# 05_-_CPU_-_PCIE.net
KiCad netlist of a schematic drawn in Altium Designer
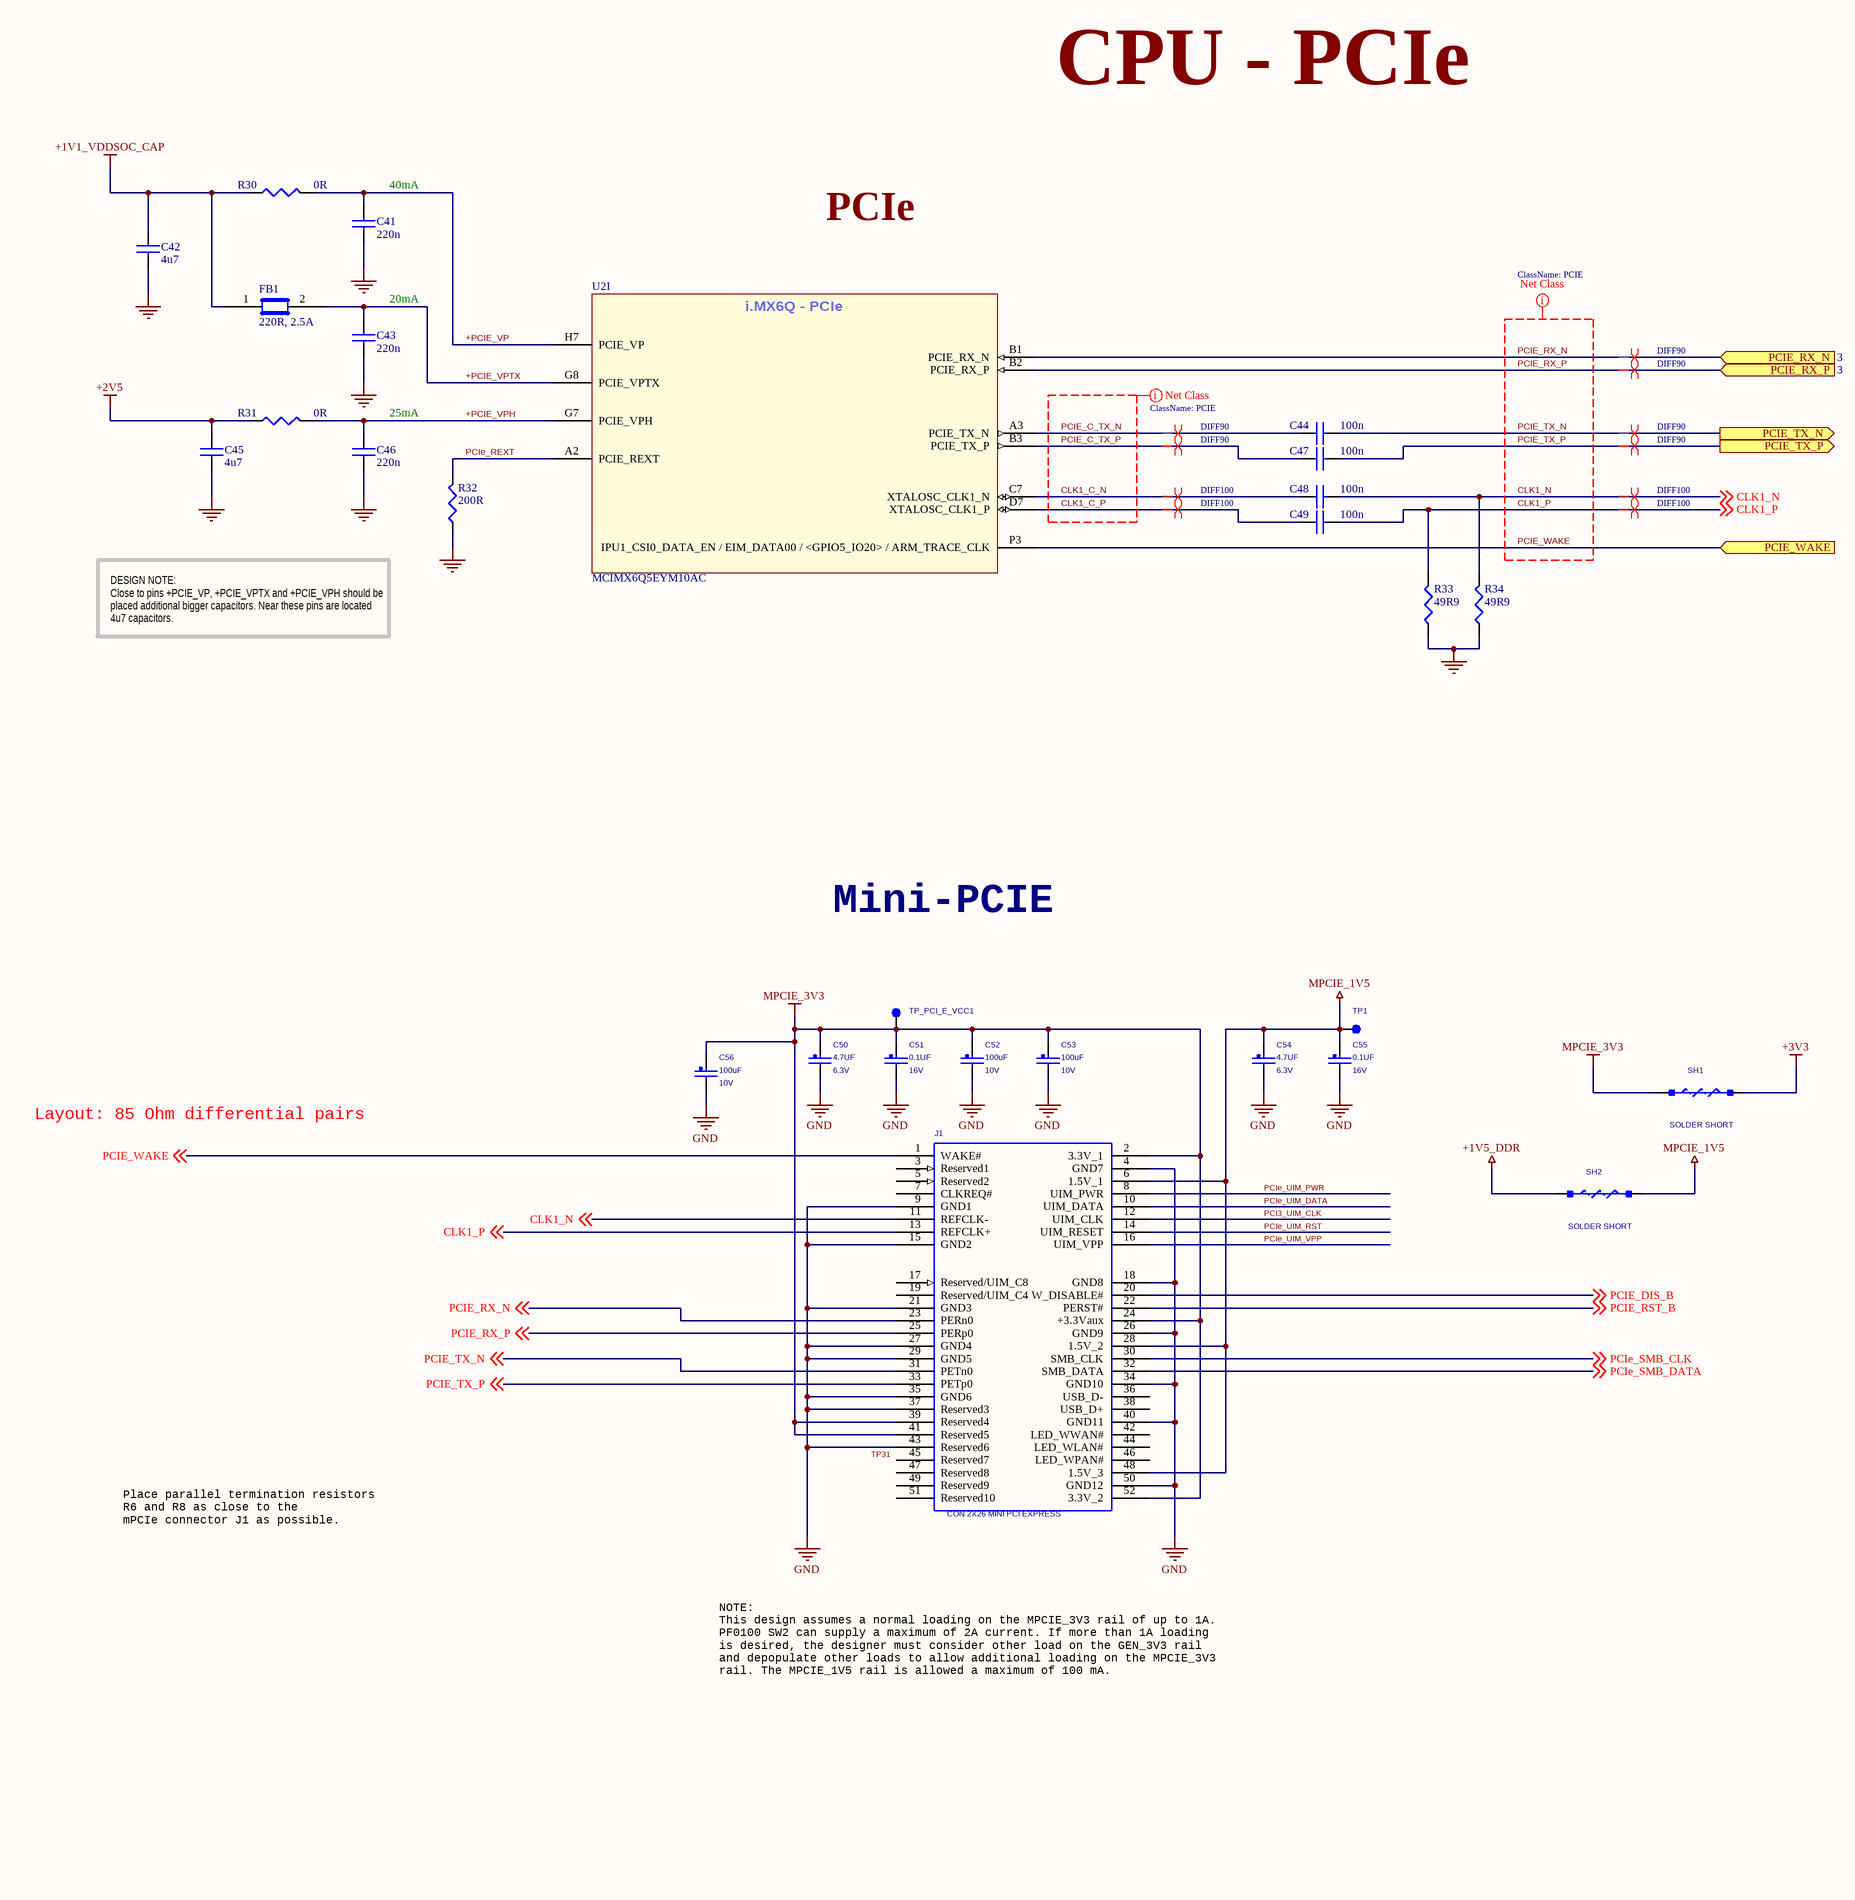
[diagram p0: [05] - CPU - PCIE.SchDoc, left]
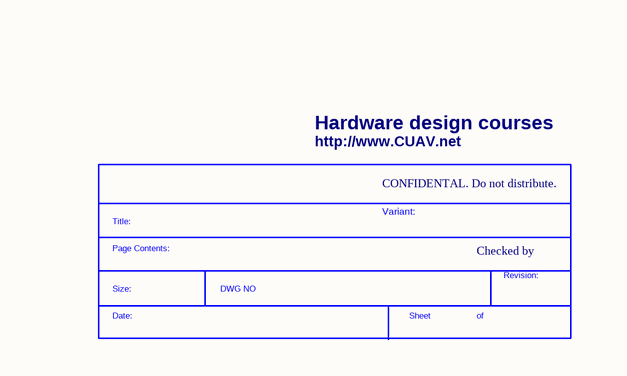
[diagram p1: [05] - CPU - PCIE.SchDoc, right]

(export (version "E")
  (design (tool "Eeschema 10.0.6"))
  (components
    (comp (ref "*") (value "SDTitleBlock") (libsource (lib "*") (part "SDTitleBlock")))
    (comp (ref "C41")
      (value "220n")
      (footprint "C0402")
      (description "CAP CER .22UF 25V X5R 20% 0402")
      (fields
        (field (name "MANUFACTURER") "TDK Corporation")
        (field (name "MANUFACTURER PART NUMBER") "C1005X5R1E224M")
      )
      (libsource (lib "Integrated_Library_RF_FEB_2012") (part "C1005X5R1E224M"))
    )
    (comp (ref "C42")
      (value "4u7")
      (footprint "0603c")
      (description "CAP CER 4.7UF 10V 20% X5R 0402")
      (fields
        (field (name "MANUFACTURER") "TDK Corporation")
        (field (name "MANUFACTURER PART NUMBER") "C1005X5R1A475M")
        (field (name ".CHECKED PCB") "RF")
        (field (name ".CHECKED SCH") "RF")
      )
      (libsource (lib "Integrated_Library_RF_FEB_2012") (part "C1005X5R1A475M"))
    )
    (comp (ref "C43")
      (value "220n")
      (footprint "C0402")
      (description "CAP CER .22UF 25V X5R 20% 0402")
      (fields
        (field (name "MANUFACTURER") "TDK Corporation")
        (field (name "MANUFACTURER PART NUMBER") "C1005X5R1E224M")
      )
      (libsource (lib "Integrated_Library_RF_FEB_2012") (part "C1005X5R1E224M"))
    )
    (comp (ref "C44")
      (value "100n")
      (footprint "C0402")
      (description "CAP CER .10UF 50V X5R 10% 0402")
      (fields
        (field (name "MANUFACTURER") "TDK Corporation")
        (field (name "MANUFACTURER PART NUMBER") "C1005X5R1H104K")
      )
      (libsource (lib "Integrated_Library_RF_FEB_2012") (part "C1005X5R1H104K"))
    )
    (comp (ref "C45")
      (value "4u7")
      (footprint "C0402")
      (description "CAP CER 4.7UF 10V 20% X5R 0402")
      (fields
        (field (name "MANUFACTURER") "TDK Corporation")
        (field (name "MANUFACTURER PART NUMBER") "C1005X5R1A475M")
        (field (name ".CHECKED PCB") "RF")
        (field (name ".CHECKED SCH") "RF")
      )
      (libsource (lib "Integrated_Library_RF_FEB_2012") (part "C1005X5R1A475M"))
    )
    (comp (ref "C46")
      (value "220n")
      (footprint "C0402")
      (description "CAP CER .22UF 25V X5R 20% 0402")
      (fields
        (field (name "MANUFACTURER") "TDK Corporation")
        (field (name "MANUFACTURER PART NUMBER") "C1005X5R1E224M")
      )
      (libsource (lib "Integrated_Library_RF_FEB_2012") (part "C1005X5R1E224M"))
    )
    (comp (ref "C47")
      (value "100n")
      (footprint "C0402")
      (description "CAP CER .10UF 50V X5R 10% 0402")
      (fields
        (field (name "MANUFACTURER") "TDK Corporation")
        (field (name "MANUFACTURER PART NUMBER") "C1005X5R1H104K")
      )
      (libsource (lib "Integrated_Library_RF_FEB_2012") (part "C1005X5R1H104K"))
    )
    (comp (ref "C48")
      (value "100n")
      (footprint "0402cap")
      (description "CAP CER .10UF 50V X5R 10% 0402")
      (fields
        (field (name "MANUFACTURER") "TDK Corporation")
        (field (name "MANUFACTURER PART NUMBER") "C1005X5R1H104K")
      )
      (libsource (lib "Integrated_Library_RF_FEB_2012") (part "C1005X5R1H104K"))
    )
    (comp (ref "C49")
      (value "100n")
      (footprint "0402cap")
      (description "CAP CER .10UF 50V X5R 10% 0402")
      (fields
        (field (name "MANUFACTURER") "TDK Corporation")
        (field (name "MANUFACTURER PART NUMBER") "C1005X5R1H104K")
      )
      (libsource (lib "Integrated_Library_RF_FEB_2012") (part "C1005X5R1H104K"))
    )
    (comp (ref "C50")
      (value "4.7UF")
      (description "CAP CER 4.7UF 6.3V 10% X5R 0603")
      (fields (field (name "TOLERANCE") "10%") (field (name "WVDC") "6.3V") (field (name "VOLTAGE") "6.3V"))
      (libsource (lib "*") (part "CAP_NP"))
    )
    (comp (ref "C51")
      (value "0.1UF")
      (description "CAP CER 0.1UF 16V 10% X7R 0402")
      (fields (field (name "TOLERANCE") "10%") (field (name "WVDC") "16V") (field (name "VOLTAGE") "16V"))
      (libsource (lib "*") (part "CAP_NP"))
    )
    (comp (ref "C52")
      (value "100uF")
      (description "CAP CER 100uF 10V 20% X5R 1206")
      (fields (field (name "TOLERANCE") "20%") (field (name "WVDC") "10V") (field (name "VOLTAGE") "10V"))
      (libsource (lib "*") (part "CAP_NP"))
    )
    (comp (ref "C53")
      (value "100uF")
      (description "CAP CER 100uF 10V 20% X5R 1206")
      (fields (field (name "TOLERANCE") "20%") (field (name "WVDC") "10V") (field (name "VOLTAGE") "10V"))
      (libsource (lib "*") (part "CAP_NP"))
    )
    (comp (ref "C54")
      (value "4.7UF")
      (description "CAP CER 4.7UF 6.3V 10% X5R 0603")
      (fields (field (name "TOLERANCE") "10%") (field (name "WVDC") "6.3V") (field (name "VOLTAGE") "6.3V"))
      (libsource (lib "*") (part "CAP_NP"))
    )
    (comp (ref "C55")
      (value "0.1UF")
      (description "CAP CER 0.1UF 16V 10% X7R 0402")
      (fields (field (name "WVDC") "16V") (field (name "TOLERANCE") "10%") (field (name "VOLTAGE") "16V"))
      (libsource (lib "*") (part "CAP_NP"))
    )
    (comp (ref "C56")
      (value "100uF")
      (description "CAP CER 100uF 10V 20% X5R 1206")
      (fields (field (name "TOLERANCE") "20%") (field (name "WVDC") "10V") (field (name "VOLTAGE") "10V"))
      (libsource (lib "*") (part "CAP_NP"))
    )
    (comp (ref "FB1")
      (value "220R, 2.5A")
      (footprint "0402r")
      (description "FERRITE CHIP 220 OHM 2500MA 0603")
      (fields
        (field (name "MANUFACTURER") "Murata Electronics North America")
        (field (name "MANUFACTURER PART NUMBER") "BLM18SG221TN1D")
        (field (name ".CHECKED PCB") "RF")
        (field (name ".CHECKED SCH") "RF")
      )
      (libsource (lib "Integrated_Library_RF_FEB_2012") (part "BLM18SG221TN1D"))
    )
    (comp (ref "J1")
      (value "CON 2X26 MINI PCI EXPRESS")
      (description "CON 2X26 MINI PCI EXPRESS SMT 0.8MM SP 1136H")
      (libsource (lib "*") (part "MINI_PCI_LATCH_52P"))
    )
    (comp (ref "R30")
      (value "0R")
      (footprint "R0402")
      (description "RES 0.0 OHM 1/16W 0402 SMD")
      (fields
        (field (name "MANUFACTURER") "Yageo")
        (field (name "MANUFACTURER PART NUMBER") "RC0402JR-070RL")
      )
      (libsource (lib "Integrated_Library_RF_FEB_2012") (part "RC0402JR-070RL"))
    )
    (comp (ref "R31")
      (value "0R")
      (footprint "R0402")
      (description "RES 0.0 OHM 1/16W 0402 SMD")
      (fields
        (field (name "MANUFACTURER") "Yageo")
        (field (name "MANUFACTURER PART NUMBER") "RC0402JR-070RL")
      )
      (libsource (lib "Integrated_Library_RF_FEB_2012") (part "RC0402JR-070RL"))
    )
    (comp (ref "R32")
      (value "200R")
      (footprint "R0402")
      (description "RES 200 OHM 1/16W 1% 0402 SMD")
      (fields
        (field (name "MANUFACTURER") "Vishay Dale")
        (field (name "MANUFACTURER PART NUMBER") "CRCW0402200RFKED")
        (field (name ".CHECKED PCB") "RF, used by MM")
        (field (name ".CHECKED SCH") "MM, checked by RF")
        (field (name ".CREATOR") "MM")
      )
      (libsource (lib "Schlib_RF") (part "CRCW0402200RFKED"))
    )
    (comp (ref "R33")
      (value "49R9")
      (footprint "R0402")
      (description "RES 49.9 OHM 1/16W 1% 0402 SMD")
      (fields
        (field (name "MANUFACTURER") "Yageo")
        (field (name "MANUFACTURER PART NUMBER") "RC0402FR-0749R9L")
      )
      (libsource (lib "Integrated_Library_RF_FEB_2012") (part "RC0402FR-0749R9L"))
    )
    (comp (ref "R34")
      (value "49R9")
      (footprint "R0402")
      (description "RES 49.9 OHM 1/16W 1% 0402 SMD")
      (fields
        (field (name "MANUFACTURER") "Yageo")
        (field (name "MANUFACTURER PART NUMBER") "RC0402FR-0749R9L")
      )
      (libsource (lib "Integrated_Library_RF_FEB_2012") (part "RC0402FR-0749R9L"))
    )
    (comp (ref "SH1")
      (value "SOLDER SHORT")
      (description "SOLDER SHORT 0805  SMT NO PART TO ORDER")
      (libsource (lib "*") (part "RES_SHORT-2"))
    )
    (comp (ref "SH2")
      (value "SOLDER SHORT")
      (description "SOLDER SHORT 0805  SMT NO PART TO ORDER")
      (libsource (lib "*") (part "RES_SHORT-2"))
    )
    (comp (ref "TP1")
      (value "TEST POINT")
      (description "TEST POINT PAD 35 MIL SMT, NO PART TO ORDER")
      (libsource (lib "*") (part "Test pad"))
    )
    (comp (ref "TP_PCI_E_VCC1")
      (value "TEST POINT")
      (description "TEST POINT PAD 35 MIL SMT, NO PART TO ORDER")
      (libsource (lib "*") (part "Test pad"))
    )
    (comp (ref "U2")
      (value "MCIMX6Q5EYM10AC")
      (footprint "PBGA624")
      (description "IC MCU 32BIT ARM QUAD 624FCBGA")
      (fields
        (field (name "MANUFACTURER") "Freescale Semiconductor")
        (field (name ".CREATOR") "MM")
        (field (name ".CHECKED PCB") "MM, checked by RF")
        (field (name ".CHECKED SCH") "MM")
      )
      (libsource (lib "Schlib_RF") (part "MCIMX6Q5EYM10AC"))
    )
  )
  (nets
    (net (code "1") (name "+1V1_VDDSOC_CAP") (class "Default")
      (node (ref "C42") (pin "1") (pinfunction "1_1") (pintype "passive"))
      (node (ref "FB1") (pin "1") (pinfunction "1_1") (pintype "passive"))
      (node (ref "R30") (pin "1") (pinfunction "1_1") (pintype "passive"))
    )
    (net (code "2") (name "+1V5_DDR") (class "Default")
      (node (ref "SH2") (pin "1") (pinfunction "1_1") (pintype "passive"))
    )
    (net (code "3") (name "+2V5") (class "Default")
      (node (ref "C45") (pin "1") (pinfunction "1_1") (pintype "passive"))
      (node (ref "R31") (pin "1") (pinfunction "1_1") (pintype "passive"))
    )
    (net (code "4") (name "+3V3") (class "Default")
      (node (ref "SH1") (pin "2") (pinfunction "2_2") (pintype "passive"))
    )
    (net (code "5") (name "/+PCIE_VP") (class "Default")
      (node (ref "C41") (pin "1") (pinfunction "1_1") (pintype "passive"))
      (node (ref "R30") (pin "2") (pinfunction "2_2") (pintype "passive"))
      (node (ref "U2") (pin "H7") (pinfunction "PCIE_VP_H7") (pintype "power_in"))
    )
    (net (code "6") (name "/+PCIE_VPH") (class "Default")
      (node (ref "C46") (pin "1") (pinfunction "1_1") (pintype "passive"))
      (node (ref "R31") (pin "2") (pinfunction "2_2") (pintype "passive"))
      (node (ref "U2") (pin "G7") (pinfunction "PCIE_VPH_G7") (pintype "power_in"))
    )
    (net (code "7") (name "/+PCIE_VPTX") (class "Default")
      (node (ref "C43") (pin "1") (pinfunction "1_1") (pintype "passive"))
      (node (ref "FB1") (pin "2") (pinfunction "2_2") (pintype "passive"))
      (node (ref "U2") (pin "G8") (pinfunction "PCIE_VPTX_G8") (pintype "power_in"))
    )
    (net (code "8") (name "/CLK1_C_N") (class "Default")
      (node (ref "C48") (pin "1") (pinfunction "1_1") (pintype "passive"))
      (node (ref "U2") (pin "C7") (pinfunction "XTALOSC_CLK1_N_C7") (pintype "bidirectional"))
    )
    (net (code "9") (name "/CLK1_C_P") (class "Default")
      (node (ref "C49") (pin "1") (pinfunction "1_1") (pintype "passive"))
      (node (ref "U2") (pin "D7") (pinfunction "XTALOSC_CLK1_P_D7") (pintype "bidirectional"))
    )
    (net (code "10") (name "/PCI3_UIM_CLK") (class "Default")
      (node (ref "J1") (pin "12") (pinfunction "UIM_CLK_12") (pintype "passive"))
    )
    (net (code "11") (name "/PCIE_C_TX_N") (class "Default")
      (node (ref "C44") (pin "1") (pinfunction "1_1") (pintype "passive"))
      (node (ref "U2") (pin "A3") (pinfunction "PCIE_TX_N_A3") (pintype "output"))
    )
    (net (code "12") (name "/PCIE_C_TX_P") (class "Default")
      (node (ref "C47") (pin "1") (pinfunction "1_1") (pintype "passive"))
      (node (ref "U2") (pin "B3") (pinfunction "PCIE_TX_P_B3") (pintype "output"))
    )
    (net (code "13") (name "/PCIe_REXT") (class "Default")
      (node (ref "R32") (pin "2") (pinfunction "2_2") (pintype "passive"))
      (node (ref "U2") (pin "A2") (pinfunction "PCIE_REXT_A2") (pintype "passive"))
    )
    (net (code "14") (name "/PCIe_UIM_DATA") (class "Default")
      (node (ref "J1") (pin "10") (pinfunction "UIM_DATA_10") (pintype "passive"))
    )
    (net (code "15") (name "/PCIe_UIM_PWR") (class "Default")
      (node (ref "J1") (pin "8") (pinfunction "UIM_PWR_8") (pintype "passive"))
    )
    (net (code "16") (name "/PCIe_UIM_RST") (class "Default")
      (node (ref "J1") (pin "14") (pinfunction "UIM_RESET_14") (pintype "passive"))
    )
    (net (code "17") (name "/PCIe_UIM_VPP") (class "Default")
      (node (ref "J1") (pin "16") (pinfunction "UIM_VPP_16") (pintype "passive"))
    )
    (net (code "19") (name "CLK1_N") (class "Default")
      (node (ref "C48") (pin "2") (pinfunction "2_2") (pintype "passive"))
      (node (ref "J1") (pin "11") (pinfunction "REFCLK-_11") (pintype "passive"))
      (node (ref "R34") (pin "2") (pinfunction "2_2") (pintype "passive"))
    )
    (net (code "20") (name "CLK1_P") (class "Default")
      (node (ref "C49") (pin "2") (pinfunction "2_2") (pintype "passive"))
      (node (ref "J1") (pin "13") (pinfunction "REFCLK+_13") (pintype "passive"))
      (node (ref "R33") (pin "2") (pinfunction "2_2") (pintype "passive"))
    )
    (net (code "21") (name "GND") (class "Default")
      (node (ref "C41") (pin "2") (pinfunction "2_2") (pintype "passive"))
      (node (ref "C42") (pin "2") (pinfunction "2_2") (pintype "passive"))
      (node (ref "C43") (pin "2") (pinfunction "2_2") (pintype "passive"))
      (node (ref "C45") (pin "2") (pinfunction "2_2") (pintype "passive"))
      (node (ref "C46") (pin "2") (pinfunction "2_2") (pintype "passive"))
      (node (ref "C50") (pin "2") (pinfunction "2_2") (pintype "passive"))
      (node (ref "C51") (pin "2") (pinfunction "2_2") (pintype "passive"))
      (node (ref "C52") (pin "2") (pinfunction "2_2") (pintype "passive"))
      (node (ref "C53") (pin "2") (pinfunction "2_2") (pintype "passive"))
      (node (ref "C54") (pin "2") (pinfunction "2_2") (pintype "passive"))
      (node (ref "C55") (pin "2") (pinfunction "2_2") (pintype "passive"))
      (node (ref "C56") (pin "2") (pinfunction "2_2") (pintype "passive"))
      (node (ref "J1") (pin "15") (pinfunction "GND2_15") (pintype "passive"))
      (node (ref "J1") (pin "18") (pinfunction "GND8_18") (pintype "passive"))
      (node (ref "J1") (pin "21") (pinfunction "GND3_21") (pintype "passive"))
      (node (ref "J1") (pin "26") (pinfunction "GND9_26") (pintype "passive"))
      (node (ref "J1") (pin "27") (pinfunction "GND4_27") (pintype "passive"))
      (node (ref "J1") (pin "29") (pinfunction "GND5_29") (pintype "passive"))
      (node (ref "J1") (pin "34") (pinfunction "GND10_34") (pintype "passive"))
      (node (ref "J1") (pin "35") (pinfunction "GND6_35") (pintype "passive"))
      (node (ref "J1") (pin "37") (pinfunction "Reserved3_37") (pintype "passive"))
      (node (ref "J1") (pin "4") (pinfunction "GND7_4") (pintype "passive"))
      (node (ref "J1") (pin "40") (pinfunction "GND11_40") (pintype "passive"))
      (node (ref "J1") (pin "43") (pinfunction "Reserved6_43") (pintype "passive"))
      (node (ref "J1") (pin "50") (pinfunction "GND12_50") (pintype "passive"))
      (node (ref "J1") (pin "9") (pinfunction "GND1_9") (pintype "passive"))
      (node (ref "R32") (pin "1") (pinfunction "1_1") (pintype "passive"))
      (node (ref "R33") (pin "1") (pinfunction "1_1") (pintype "passive"))
      (node (ref "R34") (pin "1") (pinfunction "1_1") (pintype "passive"))
    )
    (net (code "22") (name "MPCIE_1V5") (class "Default")
      (node (ref "C54") (pin "1") (pinfunction "1_1") (pintype "passive"))
      (node (ref "C55") (pin "1") (pinfunction "1_1") (pintype "passive"))
      (node (ref "J1") (pin "28") (pinfunction "1.5V_2_28") (pintype "passive"))
      (node (ref "J1") (pin "48") (pinfunction "1.5V_3_48") (pintype "passive"))
      (node (ref "J1") (pin "6") (pinfunction "1.5V_1_6") (pintype "passive"))
      (node (ref "SH2") (pin "2") (pinfunction "2_2") (pintype "passive"))
      (node (ref "TP1") (pin "1") (pinfunction "Pin1_1") (pintype "passive"))
    )
    (net (code "23") (name "MPCIE_3V3") (class "Default")
      (node (ref "C50") (pin "1") (pinfunction "1_1") (pintype "passive"))
      (node (ref "C51") (pin "1") (pinfunction "1_1") (pintype "passive"))
      (node (ref "C52") (pin "1") (pinfunction "1_1") (pintype "passive"))
      (node (ref "C53") (pin "1") (pinfunction "1_1") (pintype "passive"))
      (node (ref "C56") (pin "1") (pinfunction "1_1") (pintype "passive"))
      (node (ref "J1") (pin "2") (pinfunction "3.3V_1_2") (pintype "passive"))
      (node (ref "J1") (pin "24") (pinfunction "+3.3Vaux_24") (pintype "passive"))
      (node (ref "J1") (pin "39") (pinfunction "Reserved4_39") (pintype "passive"))
      (node (ref "J1") (pin "41") (pinfunction "Reserved5_41") (pintype "passive"))
      (node (ref "J1") (pin "52") (pinfunction "3.3V_2_52") (pintype "passive"))
      (node (ref "SH1") (pin "1") (pinfunction "1_1") (pintype "passive"))
      (node (ref "TP_PCI_E_VCC1") (pin "1") (pinfunction "Pin1_1") (pintype "passive"))
    )
    (net (code "24") (name "PCIE_DIS_B") (class "Default")
      (node (ref "J1") (pin "20") (pinfunction "W_DISABLE#_20") (pintype "passive"))
    )
    (net (code "25") (name "PCIE_RST_B") (class "Default")
      (node (ref "J1") (pin "22") (pinfunction "PERST#_22") (pintype "passive"))
    )
    (net (code "26") (name "PCIE_RX_N") (class "Default")
      (node (ref "J1") (pin "23") (pinfunction "PERn0_23") (pintype "passive"))
      (node (ref "U2") (pin "B1") (pinfunction "PCIE_RX_N_B1") (pintype "input"))
    )
    (net (code "27") (name "PCIE_RX_P") (class "Default")
      (node (ref "J1") (pin "25") (pinfunction "PERp0_25") (pintype "passive"))
      (node (ref "U2") (pin "B2") (pinfunction "PCIE_RX_P_B2") (pintype "input"))
    )
    (net (code "28") (name "PCIE_TX_N") (class "Default")
      (node (ref "C44") (pin "2") (pinfunction "2_2") (pintype "passive"))
      (node (ref "J1") (pin "31") (pinfunction "PETn0_31") (pintype "passive"))
    )
    (net (code "29") (name "PCIE_TX_P") (class "Default")
      (node (ref "C47") (pin "2") (pinfunction "2_2") (pintype "passive"))
      (node (ref "J1") (pin "33") (pinfunction "PETp0_33") (pintype "passive"))
    )
    (net (code "30") (name "PCIE_WAKE") (class "Default")
      (node (ref "J1") (pin "1") (pinfunction "WAKE#_1") (pintype "passive"))
      (node (ref "U2") (pin "P3") (pinfunction "IPU1_CSI0_DATA_EN_/_EIM_DATA00_/_<GPIO5_IO20>_/_ARM_TRACE_CLK_P3") (pintype "passive"))
    )
    (net (code "31") (name "PCIe_SMB_CLK") (class "Default")
      (node (ref "J1") (pin "30") (pinfunction "SMB_CLK_30") (pintype "passive"))
    )
    (net (code "32") (name "PCIe_SMB_DATA") (class "Default")
      (node (ref "J1") (pin "32") (pinfunction "SMB_DATA_32") (pintype "passive"))
    )
    (net (code "33") (name "unconnected-(J1-CLKREQ#-Pad7)") (class "Default")
      (node (ref "J1") (pin "7") (pinfunction "CLKREQ#_7") (pintype "passive"))
    )
    (net (code "34") (name "unconnected-(J1-LED_WLAN#-Pad44)") (class "Default")
      (node (ref "J1") (pin "44") (pinfunction "LED_WLAN#_44") (pintype "passive"))
    )
    (net (code "35") (name "unconnected-(J1-LED_WPAN#-Pad46)") (class "Default")
      (node (ref "J1") (pin "46") (pinfunction "LED_WPAN#_46") (pintype "passive"))
    )
    (net (code "36") (name "unconnected-(J1-LED_WWAN#-Pad42)") (class "Default")
      (node (ref "J1") (pin "42") (pinfunction "LED_WWAN#_42") (pintype "passive"))
    )
    (net (code "37") (name "unconnected-(J1-Reserved1-Pad3)") (class "Default")
      (node (ref "J1") (pin "3") (pinfunction "Reserved1_3") (pintype "input"))
    )
    (net (code "38") (name "unconnected-(J1-Reserved2-Pad5)") (class "Default")
      (node (ref "J1") (pin "5") (pinfunction "Reserved2_5") (pintype "input"))
    )
    (net (code "39") (name "unconnected-(J1-Reserved7-Pad45)") (class "Default")
      (node (ref "J1") (pin "45") (pinfunction "Reserved7_45") (pintype "passive"))
    )
    (net (code "40") (name "unconnected-(J1-Reserved8-Pad47)") (class "Default")
      (node (ref "J1") (pin "47") (pinfunction "Reserved8_47") (pintype "passive"))
    )
    (net (code "41") (name "unconnected-(J1-Reserved9-Pad49)") (class "Default")
      (node (ref "J1") (pin "49") (pinfunction "Reserved9_49") (pintype "passive"))
    )
    (net (code "42") (name "unconnected-(J1-Reserved10-Pad51)") (class "Default")
      (node (ref "J1") (pin "51") (pinfunction "Reserved10_51") (pintype "passive"))
    )
    (net (code "43") (name "unconnected-(J1-Reserved{slash}UIM_C4-Pad19)") (class "Default")
      (node (ref "J1") (pin "19") (pinfunction "Reserved/UIM_C4_19") (pintype "passive"))
    )
    (net (code "44") (name "unconnected-(J1-Reserved{slash}UIM_C8-Pad17)") (class "Default")
      (node (ref "J1") (pin "17") (pinfunction "Reserved/UIM_C8_17") (pintype "input"))
    )
    (net (code "45") (name "unconnected-(J1-USB_D+-Pad38)") (class "Default")
      (node (ref "J1") (pin "38") (pinfunction "USB_D+_38") (pintype "passive"))
    )
    (net (code "46") (name "unconnected-(J1-USB_D--Pad36)") (class "Default")
      (node (ref "J1") (pin "36") (pinfunction "USB_D-_36") (pintype "passive"))
    )
  )
)
